# potatoduino.net
KiCad netlist of a schematic drawn in EAGLE
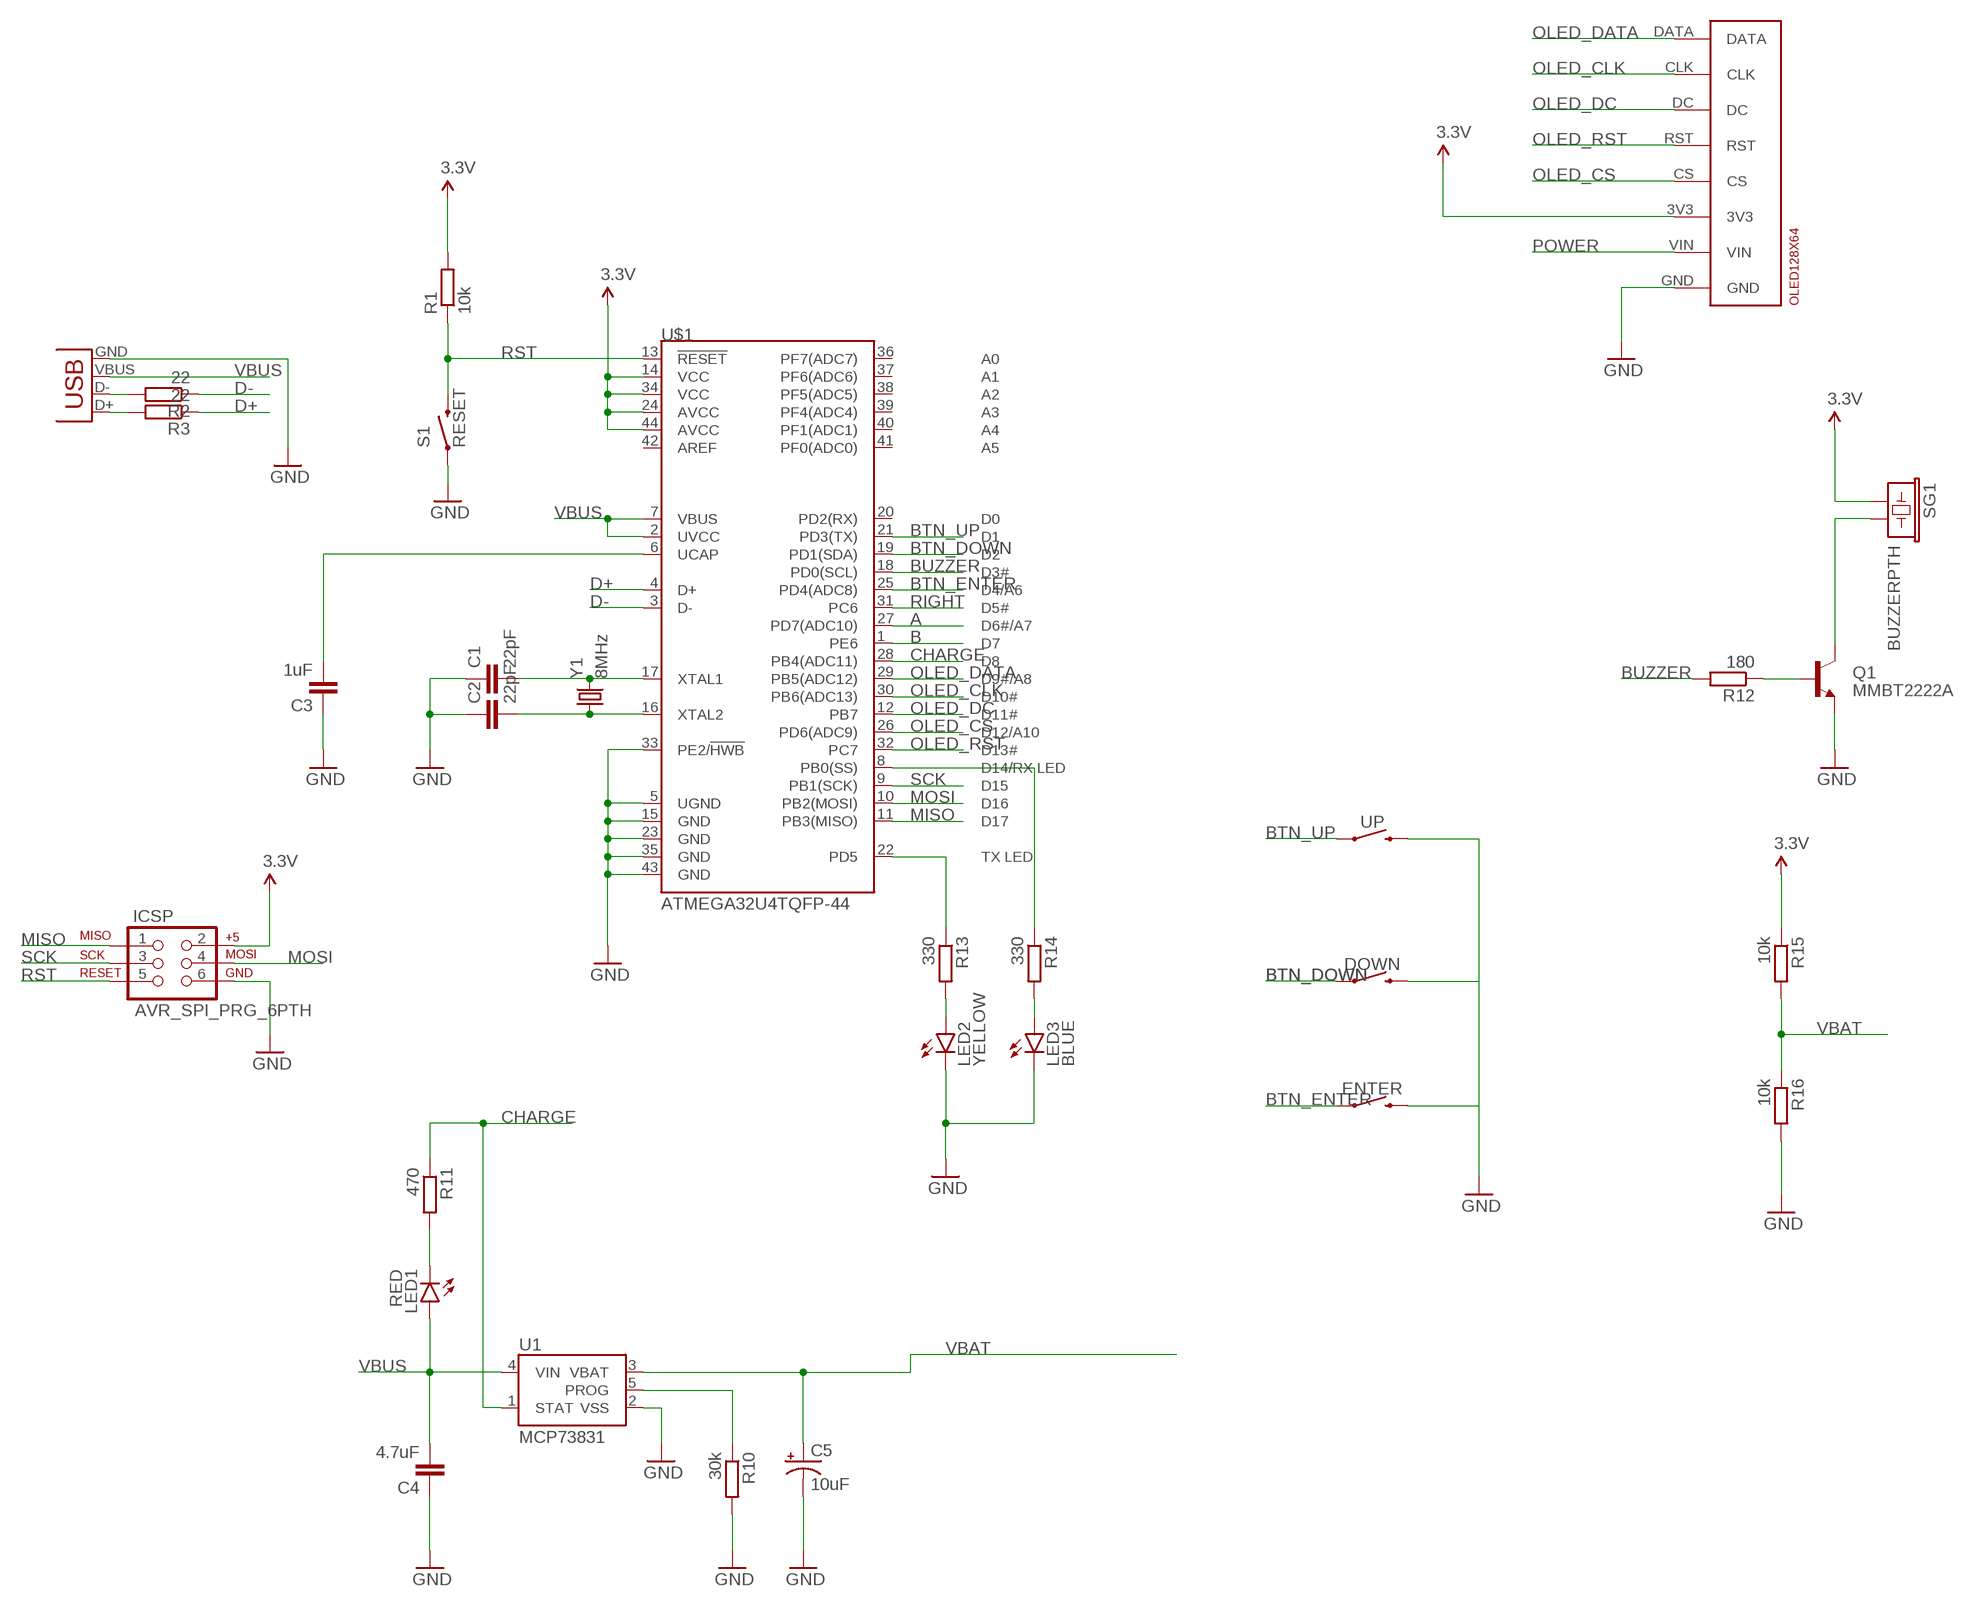
[diagram p0: schematic, sheet 1]

(export (version "E")
  (design (tool "Eeschema 10.0.6"))
  (components
    (comp (ref "C1")
      (value "22pF")
      (footprint "eagle-import:1206")
      (libsource (lib "eagle-import") (part "CAP1206"))
    )
    (comp (ref "C2")
      (value "22pF")
      (footprint "eagle-import:1206")
      (libsource (lib "eagle-import") (part "CAP1206"))
    )
    (comp (ref "C3")
      (value "1uF")
      (footprint "eagle-import:1206")
      (libsource (lib "eagle-import") (part "CAP1206"))
    )
    (comp (ref "C4")
      (value "4.7uF")
      (footprint "eagle-import:1206")
      (libsource (lib "eagle-import") (part "CAP1206"))
    )
    (comp (ref "C5")
      (value "10uF")
      (footprint "eagle-import:EIA3216")
      (libsource (lib "eagle-import") (part "CAP_POL1206"))
    )
    (comp (ref "DOWN")
      (value "MOMENTARY-SWITCH-SPST-PTH-12MM")
      (footprint "eagle-import:TACTILE_SWITCH_PTH_12MM")
      (libsource (lib "eagle-import") (part "MOMENTARY-SWITCH-SPST-PTH-12MM"))
    )
    (comp (ref "ENTER")
      (value "MOMENTARY-SWITCH-SPST-PTH-12MM")
      (footprint "eagle-import:TACTILE_SWITCH_PTH_12MM")
      (libsource (lib "eagle-import") (part "MOMENTARY-SWITCH-SPST-PTH-12MM"))
    )
    (comp (ref "ICSP")
      (value "AVR_SPI_PRG_6PTH")
      (footprint "eagle-import:2X3")
      (libsource (lib "eagle-import") (part "AVR_SPI_PRG_6PTH"))
    )
    (comp (ref "JP1")
      (value "USB-SMD-NS")
      (footprint "eagle-import:USB-MINIB-NOSTOP")
      (libsource (lib "eagle-import") (part "USB-SMD-NS"))
    )
    (comp (ref "LED1")
      (value "RED")
      (footprint "eagle-import:LED-0603")
      (libsource (lib "eagle-import") (part "LED0603"))
    )
    (comp (ref "LED2")
      (value "YELLOW")
      (footprint "eagle-import:LED-0603")
      (libsource (lib "eagle-import") (part "LED0603"))
    )
    (comp (ref "LED3")
      (value "BLUE")
      (footprint "eagle-import:LED-0603")
      (libsource (lib "eagle-import") (part "LED0603"))
    )
    (comp (ref "OLED128X64")
      (value "OLED128X64-ADAFRUIT938")
      (footprint "eagle-import:938")
      (libsource (lib "eagle-import") (part "OLED128X64-ADAFRUIT938"))
    )
    (comp (ref "Q1")
      (value "MMBT2222A")
      (footprint "eagle-import:SOT23-3")
      (libsource (lib "eagle-import") (part "TRANSISTOR_NPNMMBT2222A"))
    )
    (comp (ref "R1")
      (value "10k")
      (footprint "eagle-import:M0805")
      (libsource (lib "eagle-import") (part "R-EU_M0805"))
    )
    (comp (ref "R2")
      (value "22")
      (footprint "eagle-import:M0805")
      (libsource (lib "eagle-import") (part "R-EU_M0805"))
    )
    (comp (ref "R3")
      (value "22")
      (footprint "eagle-import:M0805")
      (libsource (lib "eagle-import") (part "R-EU_M0805"))
    )
    (comp (ref "R10")
      (value "30k")
      (footprint "eagle-import:M0805")
      (libsource (lib "eagle-import") (part "R-EU_M0805"))
    )
    (comp (ref "R11")
      (value "470")
      (footprint "eagle-import:M0805")
      (libsource (lib "eagle-import") (part "R-EU_M0805"))
    )
    (comp (ref "R12")
      (value "180")
      (footprint "eagle-import:M0805")
      (libsource (lib "eagle-import") (part "R-EU_M0805"))
    )
    (comp (ref "R13")
      (value "330")
      (footprint "eagle-import:M0805")
      (libsource (lib "eagle-import") (part "R-EU_M0805"))
    )
    (comp (ref "R14")
      (value "330")
      (footprint "eagle-import:M0805")
      (libsource (lib "eagle-import") (part "R-EU_M0805"))
    )
    (comp (ref "R15")
      (value "10k")
      (footprint "eagle-import:M0805")
      (libsource (lib "eagle-import") (part "R-EU_M0805"))
    )
    (comp (ref "R16")
      (value "10k")
      (footprint "eagle-import:M0805")
      (libsource (lib "eagle-import") (part "R-EU_M0805"))
    )
    (comp (ref "S1")
      (value "RESET")
      (footprint "eagle-import:TACTILE-SWITCH-SMD")
      (libsource (lib "eagle-import") (part "SWITCH-MOMENTARY-2SMD"))
    )
    (comp (ref "SG1")
      (value "BUZZERPTH")
      (footprint "eagle-import:BUZZER-12MM")
      (libsource (lib "eagle-import") (part "BUZZERPTH"))
    )
    (comp (ref "U$1")
      (value "ATMEGA32U4TQFP-44")
      (footprint "eagle-import:TQFP44")
      (libsource (lib "eagle-import") (part "ATMEGA32U4TQFP-44"))
    )
    (comp (ref "U1")
      (value "MCP73831")
      (footprint "eagle-import:SOT23-5")
      (libsource (lib "eagle-import") (part "MCP73831"))
    )
    (comp (ref "UP")
      (value "MOMENTARY-SWITCH-SPST-PTH-12MM")
      (footprint "eagle-import:TACTILE_SWITCH_PTH_12MM")
      (libsource (lib "eagle-import") (part "MOMENTARY-SWITCH-SPST-PTH-12MM"))
    )
    (comp (ref "Y1")
      (value "8MHz")
      (footprint "eagle-import:HC49US")
      (libsource (lib "eagle-import") (part "CRYSTALHC49US"))
    )
  )
  (nets
    (net (code "1") (name "/A") (class "Default")
      (node (ref "U$1") (pin "27") (pinfunction "PD7(ADC10)_27") (pintype "bidirectional"))
    )
    (net (code "2") (name "/B") (class "Default")
      (node (ref "U$1") (pin "1") (pinfunction "PE6_1") (pintype "bidirectional"))
    )
    (net (code "3") (name "/BTN_DOWN") (class "Default")
      (node (ref "DOWN") (pin "1") (pinfunction "1_1") (pintype "passive"))
      (node (ref "U$1") (pin "19") (pinfunction "PD1(SDA)_19") (pintype "bidirectional"))
    )
    (net (code "4") (name "/BTN_ENTER") (class "Default")
      (node (ref "ENTER") (pin "1") (pinfunction "1_1") (pintype "passive"))
      (node (ref "U$1") (pin "25") (pinfunction "PD4(ADC8)_25") (pintype "bidirectional"))
    )
    (net (code "5") (name "/BTN_UP") (class "Default")
      (node (ref "U$1") (pin "21") (pinfunction "PD3(TX)_21") (pintype "bidirectional"))
      (node (ref "UP") (pin "1") (pinfunction "1_1") (pintype "passive"))
    )
    (net (code "6") (name "/BUZZER") (class "Default")
      (node (ref "R12") (pin "2") (pinfunction "2_2") (pintype "passive"))
      (node (ref "U$1") (pin "18") (pinfunction "PD0(SCL)_18") (pintype "bidirectional"))
    )
    (net (code "7") (name "/CHARGE") (class "Default")
      (node (ref "R11") (pin "1") (pinfunction "1_1") (pintype "passive"))
      (node (ref "U$1") (pin "28") (pinfunction "PB4(ADC11)_28") (pintype "bidirectional"))
      (node (ref "U1") (pin "1") (pinfunction "STAT_1") (pintype "output"))
    )
    (net (code "8") (name "/D+") (class "Default")
      (node (ref "R3") (pin "1") (pinfunction "1_1") (pintype "passive"))
      (node (ref "U$1") (pin "4") (pinfunction "D+_4") (pintype "bidirectional"))
    )
    (net (code "9") (name "/D-") (class "Default")
      (node (ref "R2") (pin "1") (pinfunction "1_1") (pintype "passive"))
      (node (ref "U$1") (pin "3") (pinfunction "D-_3") (pintype "bidirectional"))
    )
    (net (code "10") (name "/MISO") (class "Default")
      (node (ref "ICSP") (pin "1") (pinfunction "1_1") (pintype "passive"))
      (node (ref "U$1") (pin "11") (pinfunction "PB3(MISO)_11") (pintype "bidirectional"))
    )
    (net (code "11") (name "/MOSI") (class "Default")
      (node (ref "ICSP") (pin "4") (pinfunction "4_4") (pintype "passive"))
      (node (ref "U$1") (pin "10") (pinfunction "PB2(MOSI)_10") (pintype "bidirectional"))
    )
    (net (code "12") (name "/OLED_CLK") (class "Default")
      (node (ref "OLED128X64") (pin "CLK") (pinfunction "CLK_CLK") (pintype "bidirectional"))
      (node (ref "U$1") (pin "30") (pinfunction "PB6(ADC13)_30") (pintype "bidirectional"))
    )
    (net (code "13") (name "/OLED_CS") (class "Default")
      (node (ref "OLED128X64") (pin "CS") (pinfunction "CS_CS") (pintype "bidirectional"))
      (node (ref "U$1") (pin "26") (pinfunction "PD6(ADC9)_26") (pintype "bidirectional"))
    )
    (net (code "14") (name "/OLED_DATA") (class "Default")
      (node (ref "OLED128X64") (pin "DATA") (pinfunction "DATA_DATA") (pintype "bidirectional"))
      (node (ref "U$1") (pin "29") (pinfunction "PB5(ADC12)_29") (pintype "bidirectional"))
    )
    (net (code "15") (name "/OLED_DC") (class "Default")
      (node (ref "OLED128X64") (pin "DC") (pinfunction "DC_DC") (pintype "bidirectional"))
      (node (ref "U$1") (pin "12") (pinfunction "PB7_12") (pintype "bidirectional"))
    )
    (net (code "16") (name "/OLED_RST") (class "Default")
      (node (ref "OLED128X64") (pin "RST") (pinfunction "RST_RST") (pintype "bidirectional"))
      (node (ref "U$1") (pin "32") (pinfunction "PC7_32") (pintype "bidirectional"))
    )
    (net (code "17") (name "/POWER") (class "Default")
      (node (ref "OLED128X64") (pin "VIN") (pinfunction "VIN_VIN") (pintype "bidirectional"))
    )
    (net (code "18") (name "/RIGHT") (class "Default")
      (node (ref "U$1") (pin "31") (pinfunction "PC6_31") (pintype "bidirectional"))
    )
    (net (code "19") (name "/RST") (class "Default")
      (node (ref "ICSP") (pin "5") (pinfunction "5_5") (pintype "passive"))
      (node (ref "R1") (pin "1") (pinfunction "1_1") (pintype "passive"))
      (node (ref "S1") (pin "3") (pinfunction "2_3") (pintype "passive"))
      (node (ref "U$1") (pin "13") (pinfunction "~{RESET}_13") (pintype "bidirectional"))
    )
    (net (code "20") (name "/SCK") (class "Default")
      (node (ref "ICSP") (pin "3") (pinfunction "3_3") (pintype "passive"))
      (node (ref "U$1") (pin "9") (pinfunction "PB1(SCK)_9") (pintype "bidirectional"))
    )
    (net (code "21") (name "/VBAT") (class "Default")
      (node (ref "C5") (pin "A") (pinfunction "+_A") (pintype "passive"))
      (node (ref "R15") (pin "2") (pinfunction "2_2") (pintype "passive"))
      (node (ref "R16") (pin "1") (pinfunction "1_1") (pintype "passive"))
      (node (ref "U1") (pin "3") (pinfunction "VBAT_3") (pintype "power_in"))
    )
    (net (code "22") (name "/VBUS") (class "Default")
      (node (ref "C4") (pin "2") (pinfunction "2_2") (pintype "passive"))
      (node (ref "JP1") (pin "VBUS") (pinfunction "VBUS_VBUS") (pintype "bidirectional"))
      (node (ref "LED1") (pin "A") (pinfunction "A_A") (pintype "passive"))
      (node (ref "U$1") (pin "2") (pinfunction "UVCC_2") (pintype "bidirectional"))
      (node (ref "U$1") (pin "7") (pinfunction "VBUS_7") (pintype "bidirectional"))
      (node (ref "U1") (pin "4") (pinfunction "VIN_4") (pintype "power_in"))
    )
    (net (code "23") (name "3.3V") (class "Default")
      (node (ref "ICSP") (pin "2") (pinfunction "2_2") (pintype "passive"))
      (node (ref "OLED128X64") (pin "3V3") (pinfunction "3V3_3V3") (pintype "bidirectional"))
      (node (ref "R1") (pin "2") (pinfunction "2_2") (pintype "passive"))
      (node (ref "R15") (pin "1") (pinfunction "1_1") (pintype "passive"))
      (node (ref "SG1") (pin "+") (pinfunction "1_+") (pintype "passive"))
      (node (ref "U$1") (pin "14") (pinfunction "VCC_14") (pintype "bidirectional"))
      (node (ref "U$1") (pin "24") (pinfunction "AVCC_24") (pintype "bidirectional"))
      (node (ref "U$1") (pin "34") (pinfunction "VCC_34") (pintype "bidirectional"))
      (node (ref "U$1") (pin "44") (pinfunction "AVCC_44") (pintype "bidirectional"))
    )
    (net (code "24") (name "GND") (class "Default")
      (node (ref "C1") (pin "1") (pinfunction "1_1") (pintype "passive"))
      (node (ref "C2") (pin "1") (pinfunction "1_1") (pintype "passive"))
      (node (ref "C3") (pin "1") (pinfunction "1_1") (pintype "passive"))
      (node (ref "C4") (pin "1") (pinfunction "1_1") (pintype "passive"))
      (node (ref "C5") (pin "C") (pinfunction "-_C") (pintype "passive"))
      (node (ref "DOWN") (pin "3") (pinfunction "2_3") (pintype "passive"))
      (node (ref "ENTER") (pin "3") (pinfunction "2_3") (pintype "passive"))
      (node (ref "ICSP") (pin "6") (pinfunction "6_6") (pintype "passive"))
      (node (ref "JP1") (pin "GND") (pinfunction "GND_GND") (pintype "bidirectional"))
      (node (ref "LED2") (pin "C") (pinfunction "C_C") (pintype "passive"))
      (node (ref "LED3") (pin "C") (pinfunction "C_C") (pintype "passive"))
      (node (ref "OLED128X64") (pin "GND") (pinfunction "GND_GND") (pintype "bidirectional"))
      (node (ref "Q1") (pin "2") (pinfunction "E_2") (pintype "passive"))
      (node (ref "R10") (pin "2") (pinfunction "2_2") (pintype "passive"))
      (node (ref "R16") (pin "2") (pinfunction "2_2") (pintype "passive"))
      (node (ref "S1") (pin "1") (pinfunction "1_1") (pintype "passive"))
      (node (ref "U$1") (pin "15") (pinfunction "GND_15") (pintype "bidirectional"))
      (node (ref "U$1") (pin "23") (pinfunction "GND_23") (pintype "bidirectional"))
      (node (ref "U$1") (pin "33") (pinfunction "PE2/~{HWB}_33") (pintype "bidirectional"))
      (node (ref "U$1") (pin "35") (pinfunction "GND_35") (pintype "bidirectional"))
      (node (ref "U$1") (pin "43") (pinfunction "GND_43") (pintype "bidirectional"))
      (node (ref "U$1") (pin "5") (pinfunction "UGND_5") (pintype "bidirectional"))
      (node (ref "U1") (pin "2") (pinfunction "VSS_2") (pintype "power_in"))
      (node (ref "UP") (pin "3") (pinfunction "2_3") (pintype "passive"))
    )
    (net (code "25") (name "Net-(JP1-PadD+)") (class "Default")
      (node (ref "JP1") (pin "D+") (pinfunction "D+_D+") (pintype "bidirectional"))
      (node (ref "R3") (pin "2") (pinfunction "2_2") (pintype "passive"))
    )
    (net (code "26") (name "Net-(JP1-PadD-)") (class "Default")
      (node (ref "JP1") (pin "D-") (pinfunction "D-_D-") (pintype "bidirectional"))
      (node (ref "R2") (pin "2") (pinfunction "2_2") (pintype "passive"))
    )
    (net (code "27") (name "Net-(LED1-PadC)") (class "Default")
      (node (ref "LED1") (pin "C") (pinfunction "C_C") (pintype "passive"))
      (node (ref "R11") (pin "2") (pinfunction "2_2") (pintype "passive"))
    )
    (net (code "28") (name "Net-(LED2-PadA)") (class "Default")
      (node (ref "LED2") (pin "A") (pinfunction "A_A") (pintype "passive"))
      (node (ref "R13") (pin "2") (pinfunction "2_2") (pintype "passive"))
    )
    (net (code "29") (name "Net-(LED3-PadA)") (class "Default")
      (node (ref "LED3") (pin "A") (pinfunction "A_A") (pintype "passive"))
      (node (ref "R14") (pin "2") (pinfunction "2_2") (pintype "passive"))
    )
    (net (code "30") (name "Net-(Q1-B)") (class "Default")
      (node (ref "Q1") (pin "1") (pinfunction "B_1") (pintype "passive"))
      (node (ref "R12") (pin "1") (pinfunction "1_1") (pintype "passive"))
    )
    (net (code "31") (name "Net-(Q1-C)") (class "Default")
      (node (ref "Q1") (pin "3") (pinfunction "C_3") (pintype "passive"))
      (node (ref "SG1") (pin "-") (pinfunction "2_-") (pintype "passive"))
    )
    (net (code "32") (name "Net-(U$1-PB0(SS))") (class "Default")
      (node (ref "R14") (pin "1") (pinfunction "1_1") (pintype "passive"))
      (node (ref "U$1") (pin "8") (pinfunction "PB0(SS)_8") (pintype "bidirectional"))
    )
    (net (code "33") (name "Net-(U$1-PD5)") (class "Default")
      (node (ref "R13") (pin "1") (pinfunction "1_1") (pintype "passive"))
      (node (ref "U$1") (pin "22") (pinfunction "PD5_22") (pintype "bidirectional"))
    )
    (net (code "34") (name "Net-(U$1-UCAP)") (class "Default")
      (node (ref "C3") (pin "2") (pinfunction "2_2") (pintype "passive"))
      (node (ref "U$1") (pin "6") (pinfunction "UCAP_6") (pintype "bidirectional"))
    )
    (net (code "35") (name "Net-(U$1-XTAL1)") (class "Default")
      (node (ref "C1") (pin "2") (pinfunction "2_2") (pintype "passive"))
      (node (ref "U$1") (pin "17") (pinfunction "XTAL1_17") (pintype "bidirectional"))
      (node (ref "Y1") (pin "2") (pinfunction "2_2") (pintype "passive"))
    )
    (net (code "36") (name "Net-(U$1-XTAL2)") (class "Default")
      (node (ref "C2") (pin "2") (pinfunction "2_2") (pintype "passive"))
      (node (ref "U$1") (pin "16") (pinfunction "XTAL2_16") (pintype "bidirectional"))
      (node (ref "Y1") (pin "1") (pinfunction "1_1") (pintype "passive"))
    )
    (net (code "37") (name "Net-(U1-PROG)") (class "Default")
      (node (ref "R10") (pin "1") (pinfunction "1_1") (pintype "passive"))
      (node (ref "U1") (pin "5") (pinfunction "PROG_5") (pintype "input"))
    )
    (net (code "38") (name "unconnected-(U$1-AREF-Pad42)") (class "Default")
      (node (ref "U$1") (pin "42") (pinfunction "AREF_42") (pintype "bidirectional"))
    )
    (net (code "39") (name "unconnected-(U$1-PD2(RX)-Pad20)") (class "Default")
      (node (ref "U$1") (pin "20") (pinfunction "PD2(RX)_20") (pintype "bidirectional"))
    )
    (net (code "40") (name "unconnected-(U$1-PF0(ADC0)-Pad41)") (class "Default")
      (node (ref "U$1") (pin "41") (pinfunction "PF0(ADC0)_41") (pintype "bidirectional"))
    )
    (net (code "41") (name "unconnected-(U$1-PF1(ADC1)-Pad40)") (class "Default")
      (node (ref "U$1") (pin "40") (pinfunction "PF1(ADC1)_40") (pintype "bidirectional"))
    )
    (net (code "42") (name "unconnected-(U$1-PF4(ADC4)-Pad39)") (class "Default")
      (node (ref "U$1") (pin "39") (pinfunction "PF4(ADC4)_39") (pintype "bidirectional"))
    )
    (net (code "43") (name "unconnected-(U$1-PF5(ADC5)-Pad38)") (class "Default")
      (node (ref "U$1") (pin "38") (pinfunction "PF5(ADC5)_38") (pintype "bidirectional"))
    )
    (net (code "44") (name "unconnected-(U$1-PF6(ADC6)-Pad37)") (class "Default")
      (node (ref "U$1") (pin "37") (pinfunction "PF6(ADC6)_37") (pintype "bidirectional"))
    )
    (net (code "45") (name "unconnected-(U$1-PF7(ADC7)-Pad36)") (class "Default")
      (node (ref "U$1") (pin "36") (pinfunction "PF7(ADC7)_36") (pintype "bidirectional"))
    )
  )
)
